# AIO.net
KiCad netlist of a schematic drawn in EAGLE
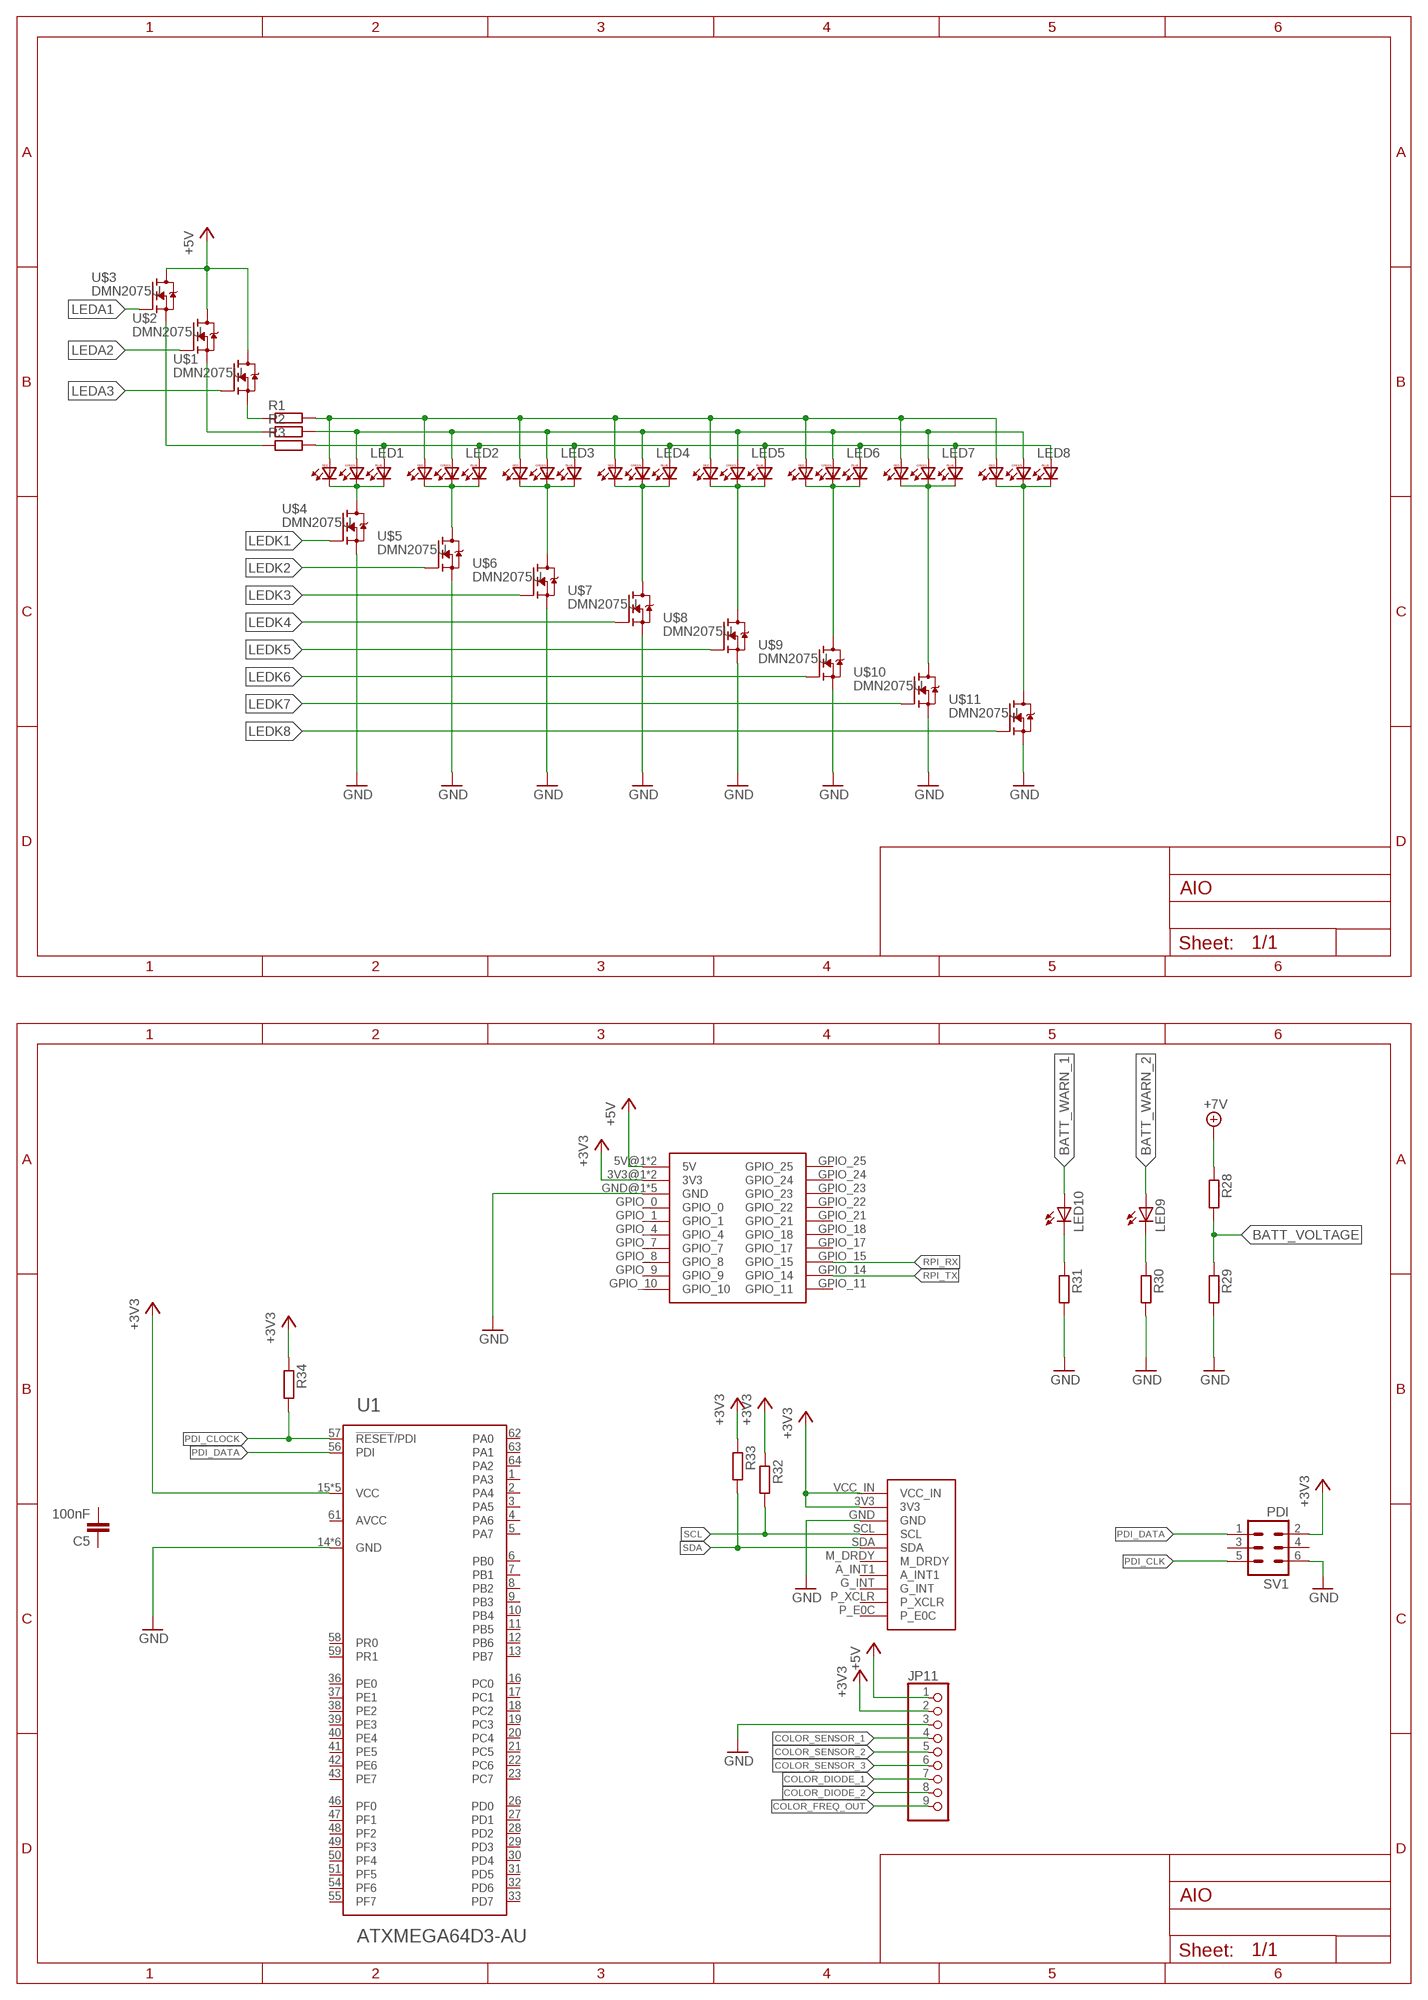
[diagram p0: schematic, sheet 1, part 1 of 2]
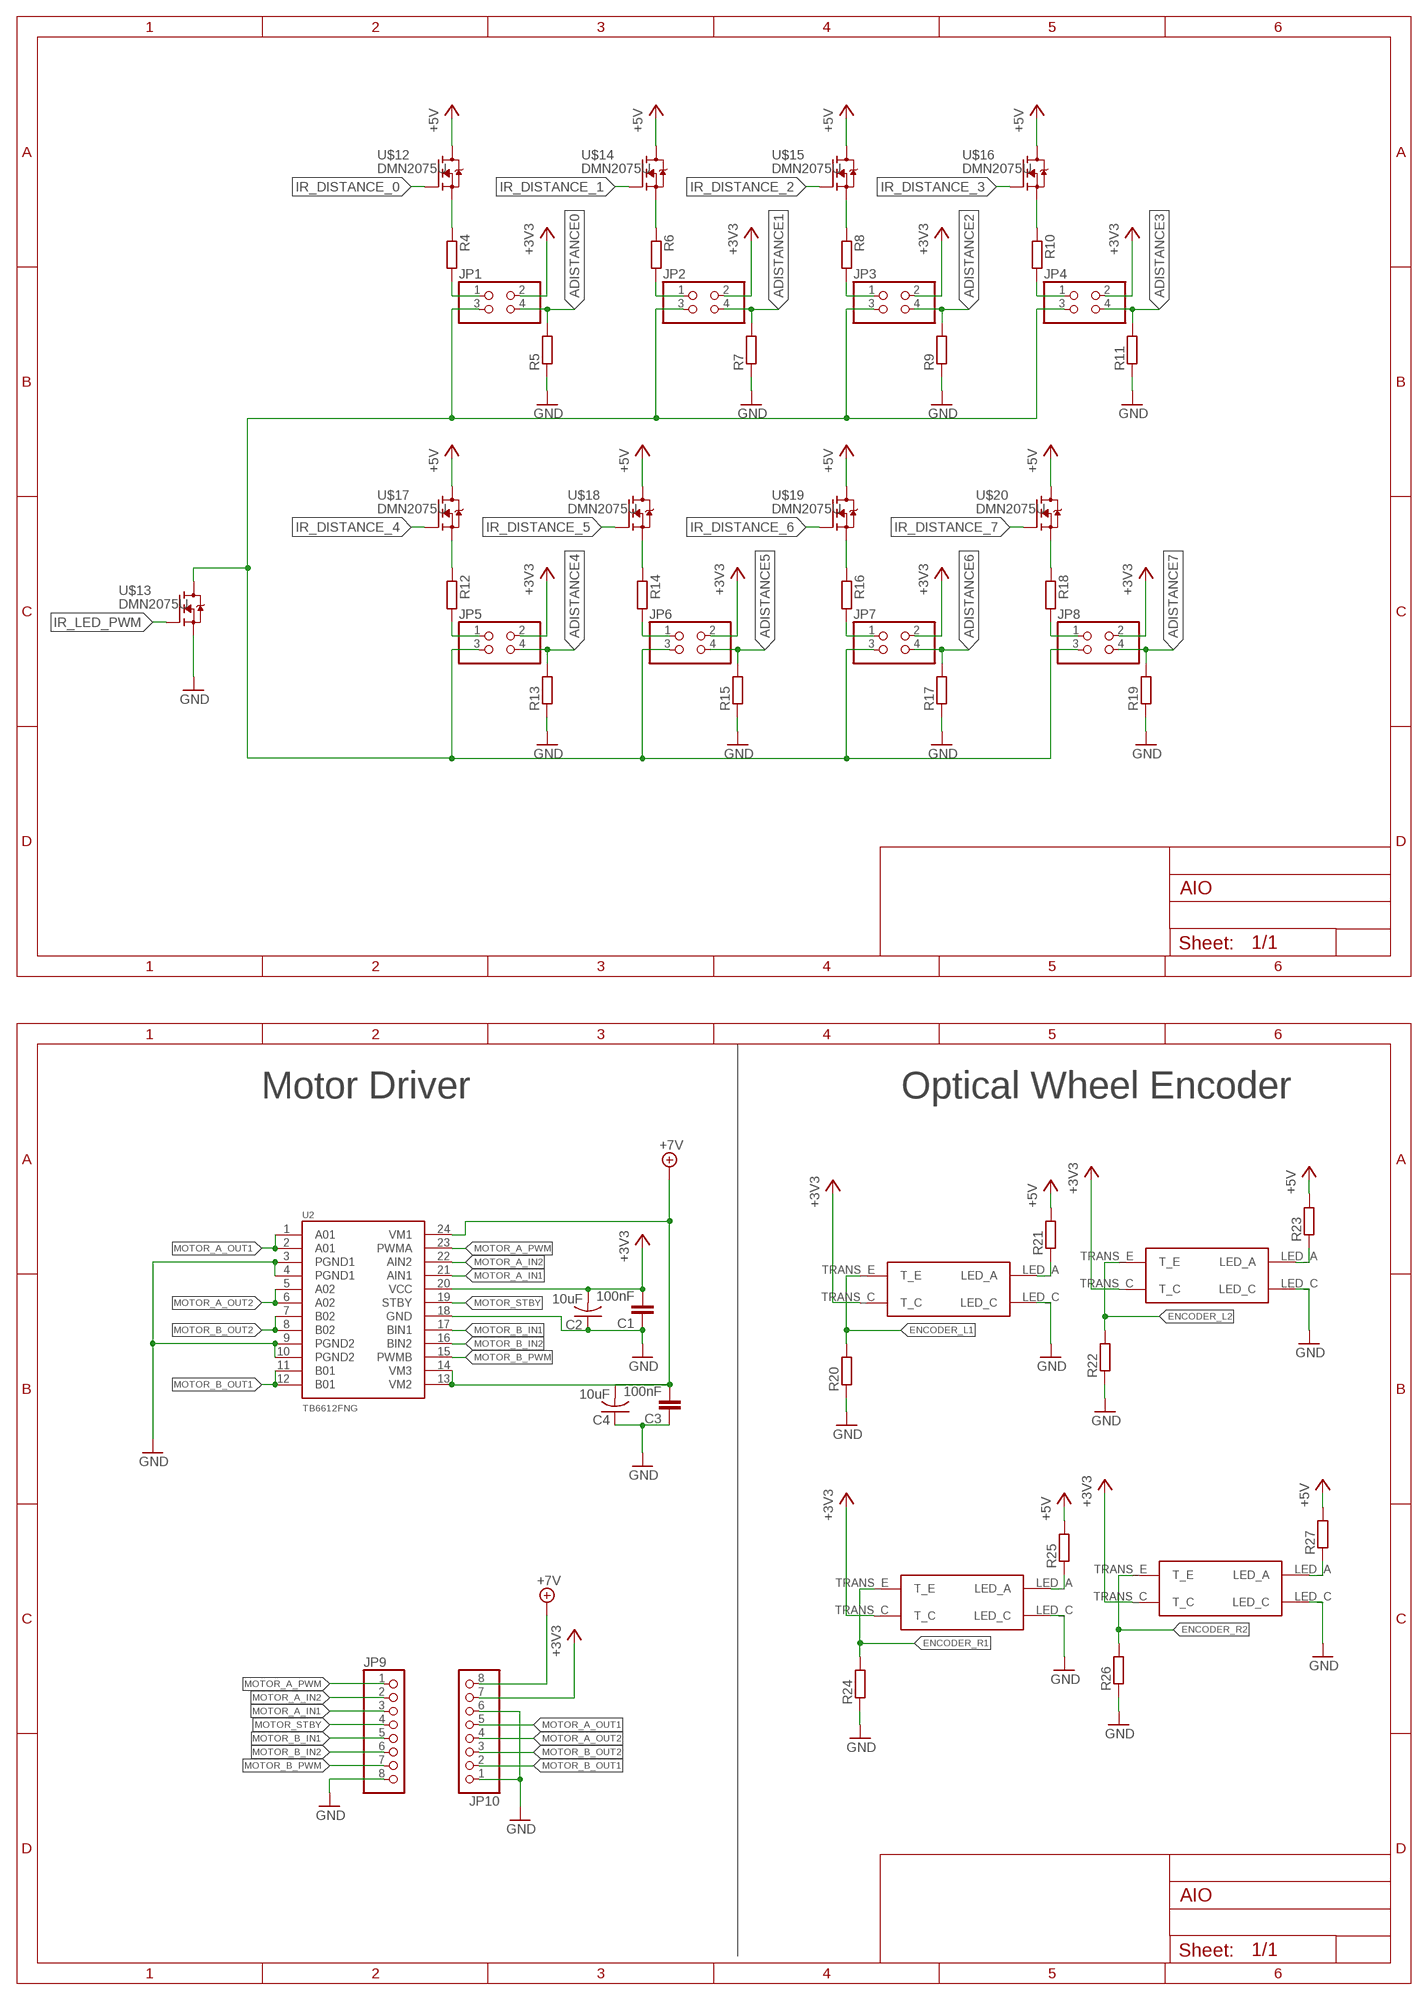
[diagram p1: schematic, sheet 1, part 2 of 2]

(export (version "E")
  (design (tool "Eeschema 10.0.6"))
  (components
    (comp (ref "C1")
      (value "100nF")
      (footprint "eagle-import:C0402")
      (libsource (lib "eagle-import") (part "C-EUC0402"))
    )
    (comp (ref "C2")
      (value "10uF")
      (footprint "eagle-import:C0402")
      (libsource (lib "eagle-import") (part "C-USC0402"))
    )
    (comp (ref "C3")
      (value "100nF")
      (footprint "eagle-import:C0402")
      (libsource (lib "eagle-import") (part "C-EUC0402"))
    )
    (comp (ref "C4")
      (value "10uF")
      (footprint "eagle-import:C0402")
      (libsource (lib "eagle-import") (part "C-USC0402"))
    )
    (comp (ref "C5")
      (value "100nF")
      (footprint "eagle-import:C0402")
      (libsource (lib "eagle-import") (part "C-EUC0402"))
    )
    (comp (ref "JP1")
      (value "PINHD-2X2/90")
      (footprint "eagle-import:2X02_90")
      (libsource (lib "eagle-import") (part "PINHD-2X2/90"))
    )
    (comp (ref "JP2")
      (value "PINHD-2X2/90")
      (footprint "eagle-import:2X02_90")
      (libsource (lib "eagle-import") (part "PINHD-2X2/90"))
    )
    (comp (ref "JP3")
      (value "PINHD-2X2/90")
      (footprint "eagle-import:2X02_90")
      (libsource (lib "eagle-import") (part "PINHD-2X2/90"))
    )
    (comp (ref "JP4")
      (value "PINHD-2X2/90")
      (footprint "eagle-import:2X02_90")
      (libsource (lib "eagle-import") (part "PINHD-2X2/90"))
    )
    (comp (ref "JP5")
      (value "PINHD-2X2/90")
      (footprint "eagle-import:2X02_90")
      (libsource (lib "eagle-import") (part "PINHD-2X2/90"))
    )
    (comp (ref "JP6")
      (value "PINHD-2X2/90")
      (footprint "eagle-import:2X02_90")
      (libsource (lib "eagle-import") (part "PINHD-2X2/90"))
    )
    (comp (ref "JP7")
      (value "PINHD-2X2/90")
      (footprint "eagle-import:2X02_90")
      (libsource (lib "eagle-import") (part "PINHD-2X2/90"))
    )
    (comp (ref "JP8")
      (value "PINHD-2X2/90")
      (footprint "eagle-import:2X02_90")
      (libsource (lib "eagle-import") (part "PINHD-2X2/90"))
    )
    (comp (ref "JP9")
      (value "PINHD-1X8")
      (footprint "eagle-import:1X08")
      (libsource (lib "eagle-import") (part "PINHD-1X8"))
    )
    (comp (ref "JP10")
      (value "PINHD-1X8")
      (footprint "eagle-import:1X08")
      (libsource (lib "eagle-import") (part "PINHD-1X8"))
    )
    (comp (ref "JP11")
      (value "PINHD-1X9")
      (footprint "eagle-import:1X09")
      (libsource (lib "eagle-import") (part "PINHD-1X9"))
    )
    (comp (ref "LED1")
      (value "F503605050")
      (footprint "eagle-import:5050LED")
      (libsource (lib "eagle-import") (part "F503605050"))
    )
    (comp (ref "LED2")
      (value "F503605050")
      (footprint "eagle-import:5050LED")
      (libsource (lib "eagle-import") (part "F503605050"))
    )
    (comp (ref "LED3")
      (value "F503605050")
      (footprint "eagle-import:5050LED")
      (libsource (lib "eagle-import") (part "F503605050"))
    )
    (comp (ref "LED4")
      (value "F503605050")
      (footprint "eagle-import:5050LED")
      (libsource (lib "eagle-import") (part "F503605050"))
    )
    (comp (ref "LED5")
      (value "F503605050")
      (footprint "eagle-import:5050LED")
      (libsource (lib "eagle-import") (part "F503605050"))
    )
    (comp (ref "LED6")
      (value "F503605050")
      (footprint "eagle-import:5050LED")
      (libsource (lib "eagle-import") (part "F503605050"))
    )
    (comp (ref "LED7")
      (value "F503605050")
      (footprint "eagle-import:5050LED")
      (libsource (lib "eagle-import") (part "F503605050"))
    )
    (comp (ref "LED8")
      (value "F503605050")
      (footprint "eagle-import:5050LED")
      (libsource (lib "eagle-import") (part "F503605050"))
    )
    (comp (ref "LED9")
      (value "LEDCHIPLED_0603")
      (footprint "eagle-import:CHIPLED_0603")
      (libsource (lib "eagle-import") (part "LEDCHIPLED_0603"))
    )
    (comp (ref "LED10")
      (value "LEDCHIPLED_0603")
      (footprint "eagle-import:CHIPLED_0603")
      (libsource (lib "eagle-import") (part "LEDCHIPLED_0603"))
    )
    (comp (ref "R1")
      (value "R-EU_R0402")
      (footprint "eagle-import:R0402")
      (libsource (lib "eagle-import") (part "R-EU_R0402"))
    )
    (comp (ref "R2")
      (value "R-EU_R0402")
      (footprint "eagle-import:R0402")
      (libsource (lib "eagle-import") (part "R-EU_R0402"))
    )
    (comp (ref "R3")
      (value "R-EU_R0402")
      (footprint "eagle-import:R0402")
      (libsource (lib "eagle-import") (part "R-EU_R0402"))
    )
    (comp (ref "R4")
      (value "R-EU_R0402")
      (footprint "eagle-import:R0402")
      (libsource (lib "eagle-import") (part "R-EU_R0402"))
    )
    (comp (ref "R5")
      (value "R-EU_R0402")
      (footprint "eagle-import:R0402")
      (libsource (lib "eagle-import") (part "R-EU_R0402"))
    )
    (comp (ref "R6")
      (value "R-EU_R0402")
      (footprint "eagle-import:R0402")
      (libsource (lib "eagle-import") (part "R-EU_R0402"))
    )
    (comp (ref "R7")
      (value "R-EU_R0402")
      (footprint "eagle-import:R0402")
      (libsource (lib "eagle-import") (part "R-EU_R0402"))
    )
    (comp (ref "R8")
      (value "R-EU_R0402")
      (footprint "eagle-import:R0402")
      (libsource (lib "eagle-import") (part "R-EU_R0402"))
    )
    (comp (ref "R9")
      (value "R-EU_R0402")
      (footprint "eagle-import:R0402")
      (libsource (lib "eagle-import") (part "R-EU_R0402"))
    )
    (comp (ref "R10")
      (value "R-EU_R0402")
      (footprint "eagle-import:R0402")
      (libsource (lib "eagle-import") (part "R-EU_R0402"))
    )
    (comp (ref "R11")
      (value "R-EU_R0402")
      (footprint "eagle-import:R0402")
      (libsource (lib "eagle-import") (part "R-EU_R0402"))
    )
    (comp (ref "R12")
      (value "R-EU_R0402")
      (footprint "eagle-import:R0402")
      (libsource (lib "eagle-import") (part "R-EU_R0402"))
    )
    (comp (ref "R13")
      (value "R-EU_R0402")
      (footprint "eagle-import:R0402")
      (libsource (lib "eagle-import") (part "R-EU_R0402"))
    )
    (comp (ref "R14")
      (value "R-EU_R0402")
      (footprint "eagle-import:R0402")
      (libsource (lib "eagle-import") (part "R-EU_R0402"))
    )
    (comp (ref "R15")
      (value "R-EU_R0402")
      (footprint "eagle-import:R0402")
      (libsource (lib "eagle-import") (part "R-EU_R0402"))
    )
    (comp (ref "R16")
      (value "R-EU_R0402")
      (footprint "eagle-import:R0402")
      (libsource (lib "eagle-import") (part "R-EU_R0402"))
    )
    (comp (ref "R17")
      (value "R-EU_R0402")
      (footprint "eagle-import:R0402")
      (libsource (lib "eagle-import") (part "R-EU_R0402"))
    )
    (comp (ref "R18")
      (value "R-EU_R0402")
      (footprint "eagle-import:R0402")
      (libsource (lib "eagle-import") (part "R-EU_R0402"))
    )
    (comp (ref "R19")
      (value "R-EU_R0402")
      (footprint "eagle-import:R0402")
      (libsource (lib "eagle-import") (part "R-EU_R0402"))
    )
    (comp (ref "R20")
      (value "R-EU_R0402")
      (footprint "eagle-import:R0402")
      (libsource (lib "eagle-import") (part "R-EU_R0402"))
    )
    (comp (ref "R21")
      (value "R-EU_R0402")
      (footprint "eagle-import:R0402")
      (libsource (lib "eagle-import") (part "R-EU_R0402"))
    )
    (comp (ref "R22")
      (value "R-EU_R0402")
      (footprint "eagle-import:R0402")
      (libsource (lib "eagle-import") (part "R-EU_R0402"))
    )
    (comp (ref "R23")
      (value "R-EU_R0402")
      (footprint "eagle-import:R0402")
      (libsource (lib "eagle-import") (part "R-EU_R0402"))
    )
    (comp (ref "R24")
      (value "R-EU_R0402")
      (footprint "eagle-import:R0402")
      (libsource (lib "eagle-import") (part "R-EU_R0402"))
    )
    (comp (ref "R25")
      (value "R-EU_R0402")
      (footprint "eagle-import:R0402")
      (libsource (lib "eagle-import") (part "R-EU_R0402"))
    )
    (comp (ref "R26")
      (value "R-EU_R0402")
      (footprint "eagle-import:R0402")
      (libsource (lib "eagle-import") (part "R-EU_R0402"))
    )
    (comp (ref "R27")
      (value "R-EU_R0402")
      (footprint "eagle-import:R0402")
      (libsource (lib "eagle-import") (part "R-EU_R0402"))
    )
    (comp (ref "R28")
      (value "R-EU_R0402")
      (footprint "eagle-import:R0402")
      (libsource (lib "eagle-import") (part "R-EU_R0402"))
    )
    (comp (ref "R29")
      (value "R-EU_R0402")
      (footprint "eagle-import:R0402")
      (libsource (lib "eagle-import") (part "R-EU_R0402"))
    )
    (comp (ref "R30")
      (value "R-EU_R0402")
      (footprint "eagle-import:R0402")
      (libsource (lib "eagle-import") (part "R-EU_R0402"))
    )
    (comp (ref "R31")
      (value "R-EU_R0402")
      (footprint "eagle-import:R0402")
      (libsource (lib "eagle-import") (part "R-EU_R0402"))
    )
    (comp (ref "R32")
      (value "R-EU_R0402")
      (footprint "eagle-import:R0402")
      (libsource (lib "eagle-import") (part "R-EU_R0402"))
    )
    (comp (ref "R33")
      (value "R-EU_R0402")
      (footprint "eagle-import:R0402")
      (libsource (lib "eagle-import") (part "R-EU_R0402"))
    )
    (comp (ref "R34")
      (value "R-EU_R0402")
      (footprint "eagle-import:R0402")
      (libsource (lib "eagle-import") (part "R-EU_R0402"))
    )
    (comp (ref "SV1")
      (value "PDI")
      (footprint "eagle-import:ML6")
      (libsource (lib "eagle-import") (part "ML6"))
    )
    (comp (ref "U$1")
      (value "DMN2075U")
      (footprint "eagle-import:SOT95P240X112-3N")
      (libsource (lib "eagle-import") (part "DMN2075U"))
    )
    (comp (ref "U$2")
      (value "DMN2075U")
      (footprint "eagle-import:SOT95P240X112-3N")
      (libsource (lib "eagle-import") (part "DMN2075U"))
    )
    (comp (ref "U$3")
      (value "DMN2075U")
      (footprint "eagle-import:SOT95P240X112-3N")
      (libsource (lib "eagle-import") (part "DMN2075U"))
    )
    (comp (ref "U$4")
      (value "DMN2075U")
      (footprint "eagle-import:SOT95P240X112-3N")
      (libsource (lib "eagle-import") (part "DMN2075U"))
    )
    (comp (ref "U$5")
      (value "DMN2075U")
      (footprint "eagle-import:SOT95P240X112-3N")
      (libsource (lib "eagle-import") (part "DMN2075U"))
    )
    (comp (ref "U$6")
      (value "DMN2075U")
      (footprint "eagle-import:SOT95P240X112-3N")
      (libsource (lib "eagle-import") (part "DMN2075U"))
    )
    (comp (ref "U$7")
      (value "DMN2075U")
      (footprint "eagle-import:SOT95P240X112-3N")
      (libsource (lib "eagle-import") (part "DMN2075U"))
    )
    (comp (ref "U$8")
      (value "DMN2075U")
      (footprint "eagle-import:SOT95P240X112-3N")
      (libsource (lib "eagle-import") (part "DMN2075U"))
    )
    (comp (ref "U$9")
      (value "DMN2075U")
      (footprint "eagle-import:SOT95P240X112-3N")
      (libsource (lib "eagle-import") (part "DMN2075U"))
    )
    (comp (ref "U$10")
      (value "DMN2075U")
      (footprint "eagle-import:SOT95P240X112-3N")
      (libsource (lib "eagle-import") (part "DMN2075U"))
    )
    (comp (ref "U$11")
      (value "DMN2075U")
      (footprint "eagle-import:SOT95P240X112-3N")
      (libsource (lib "eagle-import") (part "DMN2075U"))
    )
    (comp (ref "U$12")
      (value "DMN2075U")
      (footprint "eagle-import:SOT95P240X112-3N")
      (libsource (lib "eagle-import") (part "DMN2075U"))
    )
    (comp (ref "U$13")
      (value "DMN2075U")
      (footprint "eagle-import:SOT95P240X112-3N")
      (libsource (lib "eagle-import") (part "DMN2075U"))
    )
    (comp (ref "U$14")
      (value "DMN2075U")
      (footprint "eagle-import:SOT95P240X112-3N")
      (libsource (lib "eagle-import") (part "DMN2075U"))
    )
    (comp (ref "U$15")
      (value "DMN2075U")
      (footprint "eagle-import:SOT95P240X112-3N")
      (libsource (lib "eagle-import") (part "DMN2075U"))
    )
    (comp (ref "U$16")
      (value "DMN2075U")
      (footprint "eagle-import:SOT95P240X112-3N")
      (libsource (lib "eagle-import") (part "DMN2075U"))
    )
    (comp (ref "U$17")
      (value "DMN2075U")
      (footprint "eagle-import:SOT95P240X112-3N")
      (libsource (lib "eagle-import") (part "DMN2075U"))
    )
    (comp (ref "U$18")
      (value "DMN2075U")
      (footprint "eagle-import:SOT95P240X112-3N")
      (libsource (lib "eagle-import") (part "DMN2075U"))
    )
    (comp (ref "U$19")
      (value "DMN2075U")
      (footprint "eagle-import:SOT95P240X112-3N")
      (libsource (lib "eagle-import") (part "DMN2075U"))
    )
    (comp (ref "U$20")
      (value "DMN2075U")
      (footprint "eagle-import:SOT95P240X112-3N")
      (libsource (lib "eagle-import") (part "DMN2075U"))
    )
    (comp (ref "U$21")
      (value "CNY70")
      (footprint "eagle-import:CNY70")
      (libsource (lib "eagle-import") (part "CNY70"))
    )
    (comp (ref "U$22")
      (value "CNY70")
      (footprint "eagle-import:CNY70")
      (libsource (lib "eagle-import") (part "CNY70"))
    )
    (comp (ref "U$23")
      (value "CNY70")
      (footprint "eagle-import:CNY70")
      (libsource (lib "eagle-import") (part "CNY70"))
    )
    (comp (ref "U$24")
      (value "CNY70")
      (footprint "eagle-import:CNY70")
      (libsource (lib "eagle-import") (part "CNY70"))
    )
    (comp (ref "U$25")
      (value "GY-81")
      (footprint "eagle-import:GY-81")
      (libsource (lib "eagle-import") (part "GY-81"))
    )
    (comp (ref "U$26")
      (value "RASPBERRY-PI")
      (footprint "eagle-import:RASPERRRY-PI")
      (libsource (lib "eagle-import") (part "RASPBERRY-PI"))
    )
    (comp (ref "U1")
      (value "ATXMEGA64D3-AU")
      (footprint "eagle-import:TQFP-64A-64")
      (libsource (lib "eagle-import") (part "ATXMEGA64D3-AU"))
    )
    (comp (ref "U2")
      (value "TB6612FNG")
      (footprint "eagle-import:SSOP24")
      (libsource (lib "eagle-import") (part "TB6621FNG"))
    )
  )
  (nets
    (net (code "1") (name "+3V3") (class "Default")
      (node (ref "C1") (pin "2") (pinfunction "2_2") (pintype "passive"))
      (node (ref "C2") (pin "2") (pinfunction "2_2") (pintype "passive"))
      (node (ref "JP1") (pin "2") (pinfunction "2_2") (pintype "passive"))
      (node (ref "JP10") (pin "7") (pinfunction "7_7") (pintype "passive"))
      (node (ref "JP11") (pin "2") (pinfunction "2_2") (pintype "passive"))
      (node (ref "JP2") (pin "2") (pinfunction "2_2") (pintype "passive"))
      (node (ref "JP3") (pin "2") (pinfunction "2_2") (pintype "passive"))
      (node (ref "JP4") (pin "2") (pinfunction "2_2") (pintype "passive"))
      (node (ref "JP5") (pin "2") (pinfunction "2_2") (pintype "passive"))
      (node (ref "JP6") (pin "2") (pinfunction "2_2") (pintype "passive"))
      (node (ref "JP7") (pin "2") (pinfunction "2_2") (pintype "passive"))
      (node (ref "JP8") (pin "2") (pinfunction "2_2") (pintype "passive"))
      (node (ref "R32") (pin "1") (pinfunction "1_1") (pintype "passive"))
      (node (ref "R33") (pin "1") (pinfunction "1_1") (pintype "passive"))
      (node (ref "R34") (pin "1") (pinfunction "1_1") (pintype "passive"))
      (node (ref "SV1") (pin "2") (pinfunction "2_2") (pintype "passive"))
      (node (ref "U$21") (pin "TRANS_C") (pinfunction "T_C_TRANS_C") (pintype "bidirectional"))
      (node (ref "U$22") (pin "TRANS_C") (pinfunction "T_C_TRANS_C") (pintype "bidirectional"))
      (node (ref "U$23") (pin "TRANS_C") (pinfunction "T_C_TRANS_C") (pintype "bidirectional"))
      (node (ref "U$24") (pin "TRANS_C") (pinfunction "T_C_TRANS_C") (pintype "bidirectional"))
      (node (ref "U$25") (pin "3V3") (pinfunction "3V3_3V3") (pintype "bidirectional"))
      (node (ref "U$25") (pin "VCC_IN") (pinfunction "VCC_IN_VCC_IN") (pintype "bidirectional"))
      (node (ref "U$26") (pin "3V3@1") (pinfunction "3V3_3V3@1") (pintype "power_in"))
      (node (ref "U$26") (pin "3V3@2") (pinfunction "3V3_3V3@2") (pintype "power_in"))
      (node (ref "U1") (pin "15") (pinfunction "VCC_15") (pintype "power_in"))
      (node (ref "U1") (pin "25") (pinfunction "VCC_25") (pintype "power_in"))
      (node (ref "U1") (pin "35") (pinfunction "VCC_35") (pintype "power_in"))
      (node (ref "U1") (pin "45") (pinfunction "VCC_45") (pintype "power_in"))
      (node (ref "U1") (pin "53") (pinfunction "VCC_53") (pintype "power_in"))
      (node (ref "U2") (pin "20") (pinfunction "VCC_20") (pintype "bidirectional"))
    )
    (net (code "2") (name "+5V") (class "Default")
      (node (ref "JP11") (pin "1") (pinfunction "1_1") (pintype "passive"))
      (node (ref "R21") (pin "2") (pinfunction "2_2") (pintype "passive"))
      (node (ref "R23") (pin "2") (pinfunction "2_2") (pintype "passive"))
      (node (ref "R25") (pin "2") (pinfunction "2_2") (pintype "passive"))
      (node (ref "R27") (pin "2") (pinfunction "2_2") (pintype "passive"))
      (node (ref "U$1") (pin "D") (pinfunction "D_D") (pintype "passive"))
      (node (ref "U$12") (pin "D") (pinfunction "D_D") (pintype "passive"))
      (node (ref "U$14") (pin "D") (pinfunction "D_D") (pintype "passive"))
      (node (ref "U$15") (pin "D") (pinfunction "D_D") (pintype "passive"))
      (node (ref "U$16") (pin "D") (pinfunction "D_D") (pintype "passive"))
      (node (ref "U$17") (pin "D") (pinfunction "D_D") (pintype "passive"))
      (node (ref "U$18") (pin "D") (pinfunction "D_D") (pintype "passive"))
      (node (ref "U$19") (pin "D") (pinfunction "D_D") (pintype "passive"))
      (node (ref "U$2") (pin "D") (pinfunction "D_D") (pintype "passive"))
      (node (ref "U$20") (pin "D") (pinfunction "D_D") (pintype "passive"))
      (node (ref "U$26") (pin "5V@1") (pinfunction "5V_5V@1") (pintype "power_in"))
      (node (ref "U$26") (pin "5V@2") (pinfunction "5V_5V@2") (pintype "power_in"))
      (node (ref "U$3") (pin "D") (pinfunction "D_D") (pintype "passive"))
    )
    (net (code "3") (name "+7V") (class "Default")
      (node (ref "C3") (pin "2") (pinfunction "2_2") (pintype "passive"))
      (node (ref "C4") (pin "2") (pinfunction "2_2") (pintype "passive"))
      (node (ref "JP10") (pin "8") (pinfunction "8_8") (pintype "passive"))
      (node (ref "R28") (pin "1") (pinfunction "1_1") (pintype "passive"))
      (node (ref "U2") (pin "13") (pinfunction "VM2_13") (pintype "bidirectional"))
      (node (ref "U2") (pin "14") (pinfunction "VM3_14") (pintype "bidirectional"))
      (node (ref "U2") (pin "24") (pinfunction "VM1_24") (pintype "bidirectional"))
    )
    (net (code "4") (name "/AVCC") (class "Default")
      (node (ref "U1") (pin "61") (pinfunction "AVCC_61") (pintype "power_in"))
    )
    (net (code "5") (name "ADISTANCE0") (class "Default")
      (node (ref "JP1") (pin "4") (pinfunction "4_4") (pintype "passive"))
      (node (ref "R5") (pin "2") (pinfunction "2_2") (pintype "passive"))
    )
    (net (code "6") (name "ADISTANCE1") (class "Default")
      (node (ref "JP2") (pin "4") (pinfunction "4_4") (pintype "passive"))
      (node (ref "R7") (pin "2") (pinfunction "2_2") (pintype "passive"))
    )
    (net (code "7") (name "ADISTANCE2") (class "Default")
      (node (ref "JP3") (pin "4") (pinfunction "4_4") (pintype "passive"))
      (node (ref "R9") (pin "2") (pinfunction "2_2") (pintype "passive"))
    )
    (net (code "8") (name "ADISTANCE3") (class "Default")
      (node (ref "JP4") (pin "4") (pinfunction "4_4") (pintype "passive"))
      (node (ref "R11") (pin "2") (pinfunction "2_2") (pintype "passive"))
    )
    (net (code "9") (name "ADISTANCE4") (class "Default")
      (node (ref "JP5") (pin "4") (pinfunction "4_4") (pintype "passive"))
      (node (ref "R13") (pin "2") (pinfunction "2_2") (pintype "passive"))
    )
    (net (code "10") (name "ADISTANCE5") (class "Default")
      (node (ref "JP6") (pin "4") (pinfunction "4_4") (pintype "passive"))
      (node (ref "R15") (pin "2") (pinfunction "2_2") (pintype "passive"))
    )
    (net (code "11") (name "ADISTANCE6") (class "Default")
      (node (ref "JP7") (pin "4") (pinfunction "4_4") (pintype "passive"))
      (node (ref "R17") (pin "2") (pinfunction "2_2") (pintype "passive"))
    )
    (net (code "12") (name "ADISTANCE7") (class "Default")
      (node (ref "JP8") (pin "4") (pinfunction "4_4") (pintype "passive"))
      (node (ref "R19") (pin "2") (pinfunction "2_2") (pintype "passive"))
    )
    (net (code "13") (name "BATT_VOLTAGE") (class "Default")
      (node (ref "R28") (pin "2") (pinfunction "2_2") (pintype "passive"))
      (node (ref "R29") (pin "1") (pinfunction "1_1") (pintype "passive"))
    )
    (net (code "14") (name "BATT_WARN_1") (class "Default")
      (node (ref "LED10") (pin "A") (pinfunction "A_A") (pintype "passive"))
    )
    (net (code "15") (name "BATT_WARN_2") (class "Default")
      (node (ref "LED9") (pin "A") (pinfunction "A_A") (pintype "passive"))
    )
    (net (code "16") (name "COLOR_DIODE_1") (class "Default")
      (node (ref "JP11") (pin "7") (pinfunction "7_7") (pintype "passive"))
    )
    (net (code "17") (name "COLOR_DIODE_2") (class "Default")
      (node (ref "JP11") (pin "8") (pinfunction "8_8") (pintype "passive"))
    )
    (net (code "18") (name "COLOR_FREQ_OUT") (class "Default")
      (node (ref "JP11") (pin "9") (pinfunction "9_9") (pintype "passive"))
    )
    (net (code "19") (name "COLOR_SENSOR_1") (class "Default")
      (node (ref "JP11") (pin "4") (pinfunction "4_4") (pintype "passive"))
    )
    (net (code "20") (name "COLOR_SENSOR_2") (class "Default")
      (node (ref "JP11") (pin "5") (pinfunction "5_5") (pintype "passive"))
    )
    (net (code "21") (name "COLOR_SENSOR_3") (class "Default")
      (node (ref "JP11") (pin "6") (pinfunction "6_6") (pintype "passive"))
    )
    (net (code "22") (name "ENCODER_L1") (class "Default")
      (node (ref "R20") (pin "2") (pinfunction "2_2") (pintype "passive"))
      (node (ref "U$21") (pin "TRANS_E") (pinfunction "T_E_TRANS_E") (pintype "bidirectional"))
    )
    (net (code "23") (name "ENCODER_L2") (class "Default")
      (node (ref "R22") (pin "2") (pinfunction "2_2") (pintype "passive"))
      (node (ref "U$22") (pin "TRANS_E") (pinfunction "T_E_TRANS_E") (pintype "bidirectional"))
    )
    (net (code "24") (name "ENCODER_R1") (class "Default")
      (node (ref "R24") (pin "2") (pinfunction "2_2") (pintype "passive"))
      (node (ref "U$23") (pin "TRANS_E") (pinfunction "T_E_TRANS_E") (pintype "bidirectional"))
    )
    (net (code "25") (name "ENCODER_R2") (class "Default")
      (node (ref "R26") (pin "2") (pinfunction "2_2") (pintype "passive"))
      (node (ref "U$24") (pin "TRANS_E") (pinfunction "T_E_TRANS_E") (pintype "bidirectional"))
    )
    (net (code "26") (name "GND") (class "Default")
      (node (ref "C1") (pin "1") (pinfunction "1_1") (pintype "passive"))
      (node (ref "C2") (pin "1") (pinfunction "1_1") (pintype "passive"))
      (node (ref "C3") (pin "1") (pinfunction "1_1") (pintype "passive"))
      (node (ref "C4") (pin "1") (pinfunction "1_1") (pintype "passive"))
      (node (ref "JP10") (pin "1") (pinfunction "1_1") (pintype "passive"))
      (node (ref "JP10") (pin "6") (pinfunction "6_6") (pintype "passive"))
      (node (ref "JP11") (pin "3") (pinfunction "3_3") (pintype "passive"))
      (node (ref "JP9") (pin "8") (pinfunction "8_8") (pintype "passive"))
      (node (ref "R11") (pin "1") (pinfunction "1_1") (pintype "passive"))
      (node (ref "R13") (pin "1") (pinfunction "1_1") (pintype "passive"))
      (node (ref "R15") (pin "1") (pinfunction "1_1") (pintype "passive"))
      (node (ref "R17") (pin "1") (pinfunction "1_1") (pintype "passive"))
      (node (ref "R19") (pin "1") (pinfunction "1_1") (pintype "passive"))
      (node (ref "R20") (pin "1") (pinfunction "1_1") (pintype "passive"))
      (node (ref "R22") (pin "1") (pinfunction "1_1") (pintype "passive"))
      (node (ref "R24") (pin "1") (pinfunction "1_1") (pintype "passive"))
      (node (ref "R26") (pin "1") (pinfunction "1_1") (pintype "passive"))
      (node (ref "R29") (pin "2") (pinfunction "2_2") (pintype "passive"))
      (node (ref "R30") (pin "2") (pinfunction "2_2") (pintype "passive"))
      (node (ref "R31") (pin "2") (pinfunction "2_2") (pintype "passive"))
      (node (ref "R5") (pin "1") (pinfunction "1_1") (pintype "passive"))
      (node (ref "R7") (pin "1") (pinfunction "1_1") (pintype "passive"))
      (node (ref "R9") (pin "1") (pinfunction "1_1") (pintype "passive"))
      (node (ref "SV1") (pin "6") (pinfunction "6_6") (pintype "passive"))
      (node (ref "U$10") (pin "S") (pinfunction "S_S") (pintype "passive"))
      (node (ref "U$11") (pin "S") (pinfunction "S_S") (pintype "passive"))
      (node (ref "U$13") (pin "S") (pinfunction "S_S") (pintype "passive"))
      (node (ref "U$21") (pin "LED_C") (pinfunction "LED_C_LED_C") (pintype "bidirectional"))
      (node (ref "U$22") (pin "LED_C") (pinfunction "LED_C_LED_C") (pintype "bidirectional"))
      (node (ref "U$23") (pin "LED_C") (pinfunction "LED_C_LED_C") (pintype "bidirectional"))
      (node (ref "U$24") (pin "LED_C") (pinfunction "LED_C_LED_C") (pintype "bidirectional"))
      (node (ref "U$25") (pin "GND") (pinfunction "GND_GND") (pintype "bidirectional"))
      (node (ref "U$26") (pin "GND@1") (pinfunction "GND_GND@1") (pintype "power_in"))
      (node (ref "U$26") (pin "GND@2") (pinfunction "GND_GND@2") (pintype "power_in"))
      (node (ref "U$26") (pin "GND@3") (pinfunction "GND_GND@3") (pintype "power_in"))
      (node (ref "U$26") (pin "GND@4") (pinfunction "GND_GND@4") (pintype "power_in"))
      (node (ref "U$26") (pin "GND@5") (pinfunction "GND_GND@5") (pintype "power_in"))
      (node (ref "U$4") (pin "S") (pinfunction "S_S") (pintype "passive"))
      (node (ref "U$5") (pin "S") (pinfunction "S_S") (pintype "passive"))
      (node (ref "U$6") (pin "S") (pinfunction "S_S") (pintype "passive"))
      (node (ref "U$7") (pin "S") (pinfunction "S_S") (pintype "passive"))
      (node (ref "U$8") (pin "S") (pinfunction "S_S") (pintype "passive"))
      (node (ref "U$9") (pin "S") (pinfunction "S_S") (pintype "passive"))
      (node (ref "U1") (pin "14") (pinfunction "GND_14") (pintype "power_in"))
      (node (ref "U1") (pin "24") (pinfunction "GND_24") (pintype "power_in"))
      (node (ref "U1") (pin "34") (pinfunction "GND_34") (pintype "power_in"))
      (node (ref "U1") (pin "44") (pinfunction "GND_44") (pintype "power_in"))
      (node (ref "U1") (pin "52") (pinfunction "GND_52") (pintype "power_in"))
      (node (ref "U1") (pin "60") (pinfunction "GND_60") (pintype "power_in"))
      (node (ref "U2") (pin "10") (pinfunction "PGND2_10") (pintype "bidirectional"))
      (node (ref "U2") (pin "18") (pinfunction "GND_18") (pintype "bidirectional"))
      (node (ref "U2") (pin "3") (pinfunction "PGND1_3") (pintype "bidirectional"))
      (node (ref "U2") (pin "4") (pinfunction "PGND1_4") (pintype "bidirectional"))
      (node (ref "U2") (pin "9") (pinfunction "PGND2_9") (pintype "bidirectional"))
    )
    (net (code "27") (name "IR_DISTANCE_0") (class "Default")
      (node (ref "U$12") (pin "G") (pinfunction "G_G") (pintype "passive"))
    )
    (net (code "28") (name "IR_DISTANCE_1") (class "Default")
      (node (ref "U$14") (pin "G") (pinfunction "G_G") (pintype "passive"))
    )
    (net (code "29") (name "IR_DISTANCE_2") (class "Default")
      (node (ref "U$15") (pin "G") (pinfunction "G_G") (pintype "passive"))
    )
    (net (code "30") (name "IR_DISTANCE_3") (class "Default")
      (node (ref "U$16") (pin "G") (pinfunction "G_G") (pintype "passive"))
    )
    (net (code "31") (name "IR_DISTANCE_4") (class "Default")
      (node (ref "U$17") (pin "G") (pinfunction "G_G") (pintype "passive"))
    )
    (net (code "32") (name "IR_DISTANCE_5") (class "Default")
      (node (ref "U$18") (pin "G") (pinfunction "G_G") (pintype "passive"))
    )
    (net (code "33") (name "IR_DISTANCE_6") (class "Default")
      (node (ref "U$19") (pin "G") (pinfunction "G_G") (pintype "passive"))
    )
    (net (code "34") (name "IR_DISTANCE_7") (class "Default")
      (node (ref "U$20") (pin "G") (pinfunction "G_G") (pintype "passive"))
    )
    (net (code "35") (name "IR_LED_PWM") (class "Default")
      (node (ref "U$13") (pin "G") (pinfunction "G_G") (pintype "passive"))
    )
    (net (code "36") (name "LEDA1") (class "Default")
      (node (ref "U$3") (pin "G") (pinfunction "G_G") (pintype "passive"))
    )
    (net (code "37") (name "LEDA2") (class "Default")
      (node (ref "U$2") (pin "G") (pinfunction "G_G") (pintype "passive"))
    )
    (net (code "38") (name "LEDA3") (class "Default")
      (node (ref "U$1") (pin "G") (pinfunction "G_G") (pintype "passive"))
    )
    (net (code "39") (name "LEDK1") (class "Default")
      (node (ref "U$4") (pin "G") (pinfunction "G_G") (pintype "passive"))
    )
    (net (code "40") (name "LEDK2") (class "Default")
      (node (ref "U$5") (pin "G") (pinfunction "G_G") (pintype "passive"))
    )
    (net (code "41") (name "LEDK3") (class "Default")
      (node (ref "U$6") (pin "G") (pinfunction "G_G") (pintype "passive"))
    )
    (net (code "42") (name "LEDK4") (class "Default")
      (node (ref "U$7") (pin "G") (pinfunction "G_G") (pintype "passive"))
    )
    (net (code "43") (name "LEDK5") (class "Default")
      (node (ref "U$8") (pin "G") (pinfunction "G_G") (pintype "passive"))
    )
    (net (code "44") (name "LEDK6") (class "Default")
      (node (ref "U$9") (pin "G") (pinfunction "G_G") (pintype "passive"))
    )
    (net (code "45") (name "LEDK7") (class "Default")
      (node (ref "U$10") (pin "G") (pinfunction "G_G") (pintype "passive"))
    )
    (net (code "46") (name "LEDK8") (class "Default")
      (node (ref "U$11") (pin "G") (pinfunction "G_G") (pintype "passive"))
    )
    (net (code "47") (name "MOTOR_A_IN1") (class "Default")
      (node (ref "JP9") (pin "3") (pinfunction "3_3") (pintype "passive"))
      (node (ref "U2") (pin "21") (pinfunction "AIN1_21") (pintype "bidirectional"))
    )
    (net (code "48") (name "MOTOR_A_IN2") (class "Default")
      (node (ref "JP9") (pin "2") (pinfunction "2_2") (pintype "passive"))
      (node (ref "U2") (pin "22") (pinfunction "AIN2_22") (pintype "bidirectional"))
    )
    (net (code "49") (name "MOTOR_A_OUT1") (class "Default")
      (node (ref "JP10") (pin "5") (pinfunction "5_5") (pintype "passive"))
      (node (ref "U2") (pin "1") (pinfunction "A01_1") (pintype "bidirectional"))
      (node (ref "U2") (pin "2") (pinfunction "A01_2") (pintype "bidirectional"))
    )
    (net (code "50") (name "MOTOR_A_OUT2") (class "Default")
      (node (ref "JP10") (pin "4") (pinfunction "4_4") (pintype "passive"))
      (node (ref "U2") (pin "5") (pinfunction "A02_5") (pintype "bidirectional"))
      (node (ref "U2") (pin "6") (pinfunction "A02_6") (pintype "bidirectional"))
    )
    (net (code "51") (name "MOTOR_A_PWM") (class "Default")
      (node (ref "JP9") (pin "1") (pinfunction "1_1") (pintype "passive"))
      (node (ref "U2") (pin "23") (pinfunction "PWMA_23") (pintype "bidirectional"))
    )
    (net (code "52") (name "MOTOR_B_IN1") (class "Default")
      (node (ref "JP9") (pin "5") (pinfunction "5_5") (pintype "passive"))
      (node (ref "U2") (pin "17") (pinfunction "BIN1_17") (pintype "bidirectional"))
    )
    (net (code "53") (name "MOTOR_B_IN2") (class "Default")
      (node (ref "JP9") (pin "6") (pinfunction "6_6") (pintype "passive"))
      (node (ref "U2") (pin "16") (pinfunction "BIN2_16") (pintype "bidirectional"))
    )
    (net (code "54") (name "MOTOR_B_OUT1") (class "Default")
      (node (ref "JP10") (pin "2") (pinfunction "2_2") (pintype "passive"))
      (node (ref "U2") (pin "11") (pinfunction "B01_11") (pintype "bidirectional"))
      (node (ref "U2") (pin "12") (pinfunction "B01_12") (pintype "bidirectional"))
    )
    (net (code "55") (name "MOTOR_B_OUT2") (class "Default")
      (node (ref "JP10") (pin "3") (pinfunction "3_3") (pintype "passive"))
      (node (ref "U2") (pin "7") (pinfunction "B02_7") (pintype "bidirectional"))
      (node (ref "U2") (pin "8") (pinfunction "B02_8") (pintype "bidirectional"))
    )
    (net (code "56") (name "MOTOR_B_PWM") (class "Default")
      (node (ref "JP9") (pin "7") (pinfunction "7_7") (pintype "passive"))
      (node (ref "U2") (pin "15") (pinfunction "PWMB_15") (pintype "bidirectional"))
    )
    (net (code "57") (name "MOTOR_STBY") (class "Default")
      (node (ref "JP9") (pin "4") (pinfunction "4_4") (pintype "passive"))
      (node (ref "U2") (pin "19") (pinfunction "STBY_19") (pintype "bidirectional"))
    )
    (net (code "58") (name "Net-(JP1-Pad1)") (class "Default")
      (node (ref "JP1") (pin "1") (pinfunction "1_1") (pintype "passive"))
      (node (ref "R4") (pin "2") (pinfunction "2_2") (pintype "passive"))
    )
    (net (code "59") (name "Net-(JP1-Pad3)") (class "Default")
      (node (ref "JP1") (pin "3") (pinfunction "3_3") (pintype "passive"))
      (node (ref "JP2") (pin "3") (pinfunction "3_3") (pintype "passive"))
      (node (ref "JP3") (pin "3") (pinfunction "3_3") (pintype "passive"))
      (node (ref "JP4") (pin "3") (pinfunction "3_3") (pintype "passive"))
      (node (ref "JP5") (pin "3") (pinfunction "3_3") (pintype "passive"))
      (node (ref "JP6") (pin "3") (pinfunction "3_3") (pintype "passive"))
      (node (ref "JP7") (pin "3") (pinfunction "3_3") (pintype "passive"))
      (node (ref "JP8") (pin "3") (pinfunction "3_3") (pintype "passive"))
      (node (ref "U$13") (pin "D") (pinfunction "D_D") (pintype "passive"))
    )
    (net (code "60") (name "Net-(JP2-Pad1)") (class "Default")
      (node (ref "JP2") (pin "1") (pinfunction "1_1") (pintype "passive"))
      (node (ref "R6") (pin "2") (pinfunction "2_2") (pintype "passive"))
    )
    (net (code "61") (name "Net-(JP3-Pad1)") (class "Default")
      (node (ref "JP3") (pin "1") (pinfunction "1_1") (pintype "passive"))
      (node (ref "R8") (pin "2") (pinfunction "2_2") (pintype "passive"))
    )
    (net (code "62") (name "Net-(JP4-Pad1)") (class "Default")
      (node (ref "JP4") (pin "1") (pinfunction "1_1") (pintype "passive"))
      (node (ref "R10") (pin "2") (pinfunction "2_2") (pintype "passive"))
    )
    (net (code "63") (name "Net-(JP5-Pad1)") (class "Default")
      (node (ref "JP5") (pin "1") (pinfunction "1_1") (pintype "passive"))
      (node (ref "R12") (pin "2") (pinfunction "2_2") (pintype "passive"))
    )
    (net (code "64") (name "Net-(JP6-Pad1)") (class "Default")
      (node (ref "JP6") (pin "1") (pinfunction "1_1") (pintype "passive"))
      (node (ref "R14") (pin "2") (pinfunction "2_2") (pintype "passive"))
    )
    (net (code "65") (name "Net-(JP7-Pad1)") (class "Default")
      (node (ref "JP7") (pin "1") (pinfunction "1_1") (pintype "passive"))
      (node (ref "R16") (pin "2") (pinfunction "2_2") (pintype "passive"))
    )
    (net (code "66") (name "Net-(JP8-Pad1)") (class "Default")
      (node (ref "JP8") (pin "1") (pinfunction "1_1") (pintype "passive"))
      (node (ref "R18") (pin "2") (pinfunction "2_2") (pintype "passive"))
    )
    (net (code "67") (name "Net-(LED1-BA)") (class "Default")
      (node (ref "LED1") (pin "B1") (pinfunction "BA_B1") (pintype "passive"))
      (node (ref "LED2") (pin "B1") (pinfunction "BA_B1") (pintype "passive"))
      (node (ref "LED3") (pin "B1") (pinfunction "BA_B1") (pintype "passive"))
      (node (ref "LED4") (pin "B1") (pinfunction "BA_B1") (pintype "passive"))
      (node (ref "LED5") (pin "B1") (pinfunction "BA_B1") (pintype "passive"))
      (node (ref "LED6") (pin "B1") (pinfunction "BA_B1") (pintype "passive"))
      (node (ref "LED7") (pin "B1") (pinfunction "BA_B1") (pintype "passive"))
      (node (ref "LED8") (pin "B1") (pinfunction "BA_B1") (pintype "passive"))
      (node (ref "R3") (pin "2") (pinfunction "2_2") (pintype "passive"))
    )
    (net (code "68") (name "Net-(LED1-BC)") (class "Default")
      (node (ref "LED1") (pin "B2") (pinfunction "BC_B2") (pintype "passive"))
      (node (ref "LED1") (pin "G2") (pinfunction "GC_G2") (pintype "passive"))
      (node (ref "LED1") (pin "R2") (pinfunction "RC_R2") (pintype "passive"))
      (node (ref "U$4") (pin "D") (pinfunction "D_D") (pintype "passive"))
    )
    (net (code "69") (name "Net-(LED1-GA)") (class "Default")
      (node (ref "LED1") (pin "G1") (pinfunction "GA_G1") (pintype "passive"))
      (node (ref "LED2") (pin "G1") (pinfunction "GA_G1") (pintype "passive"))
      (node (ref "LED3") (pin "G1") (pinfunction "GA_G1") (pintype "passive"))
      (node (ref "LED4") (pin "G1") (pinfunction "GA_G1") (pintype "passive"))
      (node (ref "LED5") (pin "G1") (pinfunction "GA_G1") (pintype "passive"))
      (node (ref "LED6") (pin "G1") (pinfunction "GA_G1") (pintype "passive"))
      (node (ref "LED7") (pin "G1") (pinfunction "GA_G1") (pintype "passive"))
      (node (ref "LED8") (pin "G1") (pinfunction "GA_G1") (pintype "passive"))
      (node (ref "R2") (pin "2") (pinfunction "2_2") (pintype "passive"))
    )
    (net (code "70") (name "Net-(LED1-RA)") (class "Default")
      (node (ref "LED1") (pin "R1") (pinfunction "RA_R1") (pintype "passive"))
      (node (ref "LED2") (pin "R1") (pinfunction "RA_R1") (pintype "passive"))
      (node (ref "LED3") (pin "R1") (pinfunction "RA_R1") (pintype "passive"))
      (node (ref "LED4") (pin "R1") (pinfunction "RA_R1") (pintype "passive"))
      (node (ref "LED5") (pin "R1") (pinfunction "RA_R1") (pintype "passive"))
      (node (ref "LED6") (pin "R1") (pinfunction "RA_R1") (pintype "passive"))
      (node (ref "LED7") (pin "R1") (pinfunction "RA_R1") (pintype "passive"))
      (node (ref "LED8") (pin "R1") (pinfunction "RA_R1") (pintype "passive"))
      (node (ref "R1") (pin "2") (pinfunction "2_2") (pintype "passive"))
    )
    (net (code "71") (name "Net-(LED2-BC)") (class "Default")
      (node (ref "LED2") (pin "B2") (pinfunction "BC_B2") (pintype "passive"))
      (node (ref "LED2") (pin "G2") (pinfunction "GC_G2") (pintype "passive"))
      (node (ref "LED2") (pin "R2") (pinfunction "RC_R2") (pintype "passive"))
      (node (ref "U$5") (pin "D") (pinfunction "D_D") (pintype "passive"))
    )
    (net (code "72") (name "Net-(LED3-BC)") (class "Default")
      (node (ref "LED3") (pin "B2") (pinfunction "BC_B2") (pintype "passive"))
      (node (ref "LED3") (pin "G2") (pinfunction "GC_G2") (pintype "passive"))
      (node (ref "LED3") (pin "R2") (pinfunction "RC_R2") (pintype "passive"))
      (node (ref "U$6") (pin "D") (pinfunction "D_D") (pintype "passive"))
    )
    (net (code "73") (name "Net-(LED4-BC)") (class "Default")
      (node (ref "LED4") (pin "B2") (pinfunction "BC_B2") (pintype "passive"))
      (node (ref "LED4") (pin "G2") (pinfunction "GC_G2") (pintype "passive"))
      (node (ref "LED4") (pin "R2") (pinfunction "RC_R2") (pintype "passive"))
      (node (ref "U$7") (pin "D") (pinfunction "D_D") (pintype "passive"))
    )
    (net (code "74") (name "Net-(LED5-BC)") (class "Default")
      (node (ref "LED5") (pin "B2") (pinfunction "BC_B2") (pintype "passive"))
      (node (ref "LED5") (pin "G2") (pinfunction "GC_G2") (pintype "passive"))
      (node (ref "LED5") (pin "R2") (pinfunction "RC_R2") (pintype "passive"))
      (node (ref "U$8") (pin "D") (pinfunction "D_D") (pintype "passive"))
    )
    (net (code "75") (name "Net-(LED6-BC)") (class "Default")
      (node (ref "LED6") (pin "B2") (pinfunction "BC_B2") (pintype "passive"))
      (node (ref "LED6") (pin "G2") (pinfunction "GC_G2") (pintype "passive"))
      (node (ref "LED6") (pin "R2") (pinfunction "RC_R2") (pintype "passive"))
      (node (ref "U$9") (pin "D") (pinfunction "D_D") (pintype "passive"))
    )
    (net (code "76") (name "Net-(LED7-BC)") (class "Default")
      (node (ref "LED7") (pin "B2") (pinfunction "BC_B2") (pintype "passive"))
      (node (ref "LED7") (pin "G2") (pinfunction "GC_G2") (pintype "passive"))
      (node (ref "LED7") (pin "R2") (pinfunction "RC_R2") (pintype "passive"))
      (node (ref "U$10") (pin "D") (pinfunction "D_D") (pintype "passive"))
    )
    (net (code "77") (name "Net-(LED8-BC)") (class "Default")
      (node (ref "LED8") (pin "B2") (pinfunction "BC_B2") (pintype "passive"))
      (node (ref "LED8") (pin "G2") (pinfunction "GC_G2") (pintype "passive"))
      (node (ref "LED8") (pin "R2") (pinfunction "RC_R2") (pintype "passive"))
      (node (ref "U$11") (pin "D") (pinfunction "D_D") (pintype "passive"))
    )
    (net (code "78") (name "Net-(LED9-PadC)") (class "Default")
      (node (ref "LED9") (pin "C") (pinfunction "C_C") (pintype "passive"))
      (node (ref "R30") (pin "1") (pinfunction "1_1") (pintype "passive"))
    )
    (net (code "79") (name "Net-(LED10-PadC)") (class "Default")
      (node (ref "LED10") (pin "C") (pinfunction "C_C") (pintype "passive"))
      (node (ref "R31") (pin "1") (pinfunction "1_1") (pintype "passive"))
    )
    (net (code "80") (name "Net-(R1-Pad1)") (class "Default")
      (node (ref "R1") (pin "1") (pinfunction "1_1") (pintype "passive"))
      (node (ref "U$1") (pin "S") (pinfunction "S_S") (pintype "passive"))
    )
    (net (code "81") (name "Net-(R2-Pad1)") (class "Default")
      (node (ref "R2") (pin "1") (pinfunction "1_1") (pintype "passive"))
      (node (ref "U$2") (pin "S") (pinfunction "S_S") (pintype "passive"))
    )
    (net (code "82") (name "Net-(R3-Pad1)") (class "Default")
      (node (ref "R3") (pin "1") (pinfunction "1_1") (pintype "passive"))
      (node (ref "U$3") (pin "S") (pinfunction "S_S") (pintype "passive"))
    )
    (net (code "83") (name "Net-(R4-Pad1)") (class "Default")
      (node (ref "R4") (pin "1") (pinfunction "1_1") (pintype "passive"))
      (node (ref "U$12") (pin "S") (pinfunction "S_S") (pintype "passive"))
    )
    (net (code "84") (name "Net-(R6-Pad1)") (class "Default")
      (node (ref "R6") (pin "1") (pinfunction "1_1") (pintype "passive"))
      (node (ref "U$14") (pin "S") (pinfunction "S_S") (pintype "passive"))
    )
    (net (code "85") (name "Net-(R8-Pad1)") (class "Default")
      (node (ref "R8") (pin "1") (pinfunction "1_1") (pintype "passive"))
      (node (ref "U$15") (pin "S") (pinfunction "S_S") (pintype "passive"))
    )
    (net (code "86") (name "Net-(R10-Pad1)") (class "Default")
      (node (ref "R10") (pin "1") (pinfunction "1_1") (pintype "passive"))
      (node (ref "U$16") (pin "S") (pinfunction "S_S") (pintype "passive"))
    )
    (net (code "87") (name "Net-(R12-Pad1)") (class "Default")
      (node (ref "R12") (pin "1") (pinfunction "1_1") (pintype "passive"))
      (node (ref "U$17") (pin "S") (pinfunction "S_S") (pintype "passive"))
    )
    (net (code "88") (name "Net-(R14-Pad1)") (class "Default")
      (node (ref "R14") (pin "1") (pinfunction "1_1") (pintype "passive"))
      (node (ref "U$18") (pin "S") (pinfunction "S_S") (pintype "passive"))
    )
    (net (code "89") (name "Net-(R16-Pad1)") (class "Default")
      (node (ref "R16") (pin "1") (pinfunction "1_1") (pintype "passive"))
      (node (ref "U$19") (pin "S") (pinfunction "S_S") (pintype "passive"))
    )
    (net (code "90") (name "Net-(R18-Pad1)") (class "Default")
      (node (ref "R18") (pin "1") (pinfunction "1_1") (pintype "passive"))
      (node (ref "U$20") (pin "S") (pinfunction "S_S") (pintype "passive"))
    )
    (net (code "91") (name "Net-(R21-Pad1)") (class "Default")
      (node (ref "R21") (pin "1") (pinfunction "1_1") (pintype "passive"))
      (node (ref "U$21") (pin "LED_A") (pinfunction "LED_A_LED_A") (pintype "bidirectional"))
    )
    (net (code "92") (name "Net-(R23-Pad1)") (class "Default")
      (node (ref "R23") (pin "1") (pinfunction "1_1") (pintype "passive"))
      (node (ref "U$22") (pin "LED_A") (pinfunction "LED_A_LED_A") (pintype "bidirectional"))
    )
    (net (code "93") (name "Net-(R25-Pad1)") (class "Default")
      (node (ref "R25") (pin "1") (pinfunction "1_1") (pintype "passive"))
      (node (ref "U$23") (pin "LED_A") (pinfunction "LED_A_LED_A") (pintype "bidirectional"))
    )
    (net (code "94") (name "Net-(R27-Pad1)") (class "Default")
      (node (ref "R27") (pin "1") (pinfunction "1_1") (pintype "passive"))
      (node (ref "U$24") (pin "LED_A") (pinfunction "LED_A_LED_A") (pintype "bidirectional"))
    )
    (net (code "95") (name "PDI_CLK") (class "Default")
      (node (ref "SV1") (pin "5") (pinfunction "5_5") (pintype "passive"))
    )
    (net (code "96") (name "PDI_CLOCK") (class "Default")
      (node (ref "R34") (pin "2") (pinfunction "2_2") (pintype "passive"))
      (node (ref "U1") (pin "57") (pinfunction "~{RESET}/PDI_57") (pintype "bidirectional"))
    )
    (net (code "97") (name "PDI_DATA") (class "Default")
      (node (ref "SV1") (pin "1") (pinfunction "1_1") (pintype "passive"))
      (node (ref "U1") (pin "56") (pinfunction "PDI_56") (pintype "bidirectional"))
    )
    (net (code "98") (name "RPI_RX") (class "Default")
      (node (ref "U$26") (pin "GPIO_15") (pinfunction "GPIO_15_GPIO_15") (pintype "bidirectional"))
    )
    (net (code "99") (name "RPI_TX") (class "Default")
      (node (ref "U$26") (pin "GPIO_14") (pinfunction "GPIO_14_GPIO_14") (pintype "bidirectional"))
    )
    (net (code "100") (name "SCL") (class "Default")
      (node (ref "R32") (pin "2") (pinfunction "2_2") (pintype "passive"))
      (node (ref "U$25") (pin "SCL") (pinfunction "SCL_SCL") (pintype "bidirectional"))
    )
    (net (code "101") (name "SDA") (class "Default")
      (node (ref "R33") (pin "2") (pinfunction "2_2") (pintype "passive"))
      (node (ref "U$25") (pin "SDA") (pinfunction "SDA_SDA") (pintype "bidirectional"))
    )
    (net (code "102") (name "unconnected-(C5-Pad1)") (class "Default")
      (node (ref "C5") (pin "1") (pinfunction "1_1") (pintype "passive"))
    )
    (net (code "103") (name "unconnected-(C5-Pad2)") (class "Default")
      (node (ref "C5") (pin "2") (pinfunction "2_2") (pintype "passive"))
    )
    (net (code "104") (name "unconnected-(SV1-Pad3)") (class "Default")
      (node (ref "SV1") (pin "3") (pinfunction "3_3") (pintype "passive"))
    )
    (net (code "105") (name "unconnected-(SV1-Pad4)") (class "Default")
      (node (ref "SV1") (pin "4") (pinfunction "4_4") (pintype "passive"))
    )
    (net (code "106") (name "unconnected-(U$25-PadA_INT1)") (class "Default")
      (node (ref "U$25") (pin "A_INT1") (pinfunction "A_INT1_A_INT1") (pintype "bidirectional"))
    )
    (net (code "107") (name "unconnected-(U$25-PadG_INT)") (class "Default")
      (node (ref "U$25") (pin "G_INT") (pinfunction "G_INT_G_INT") (pintype "bidirectional"))
    )
    (net (code "108") (name "unconnected-(U$25-PadM_DRDY)") (class "Default")
      (node (ref "U$25") (pin "M_DRDY") (pinfunction "M_DRDY_M_DRDY") (pintype "bidirectional"))
    )
    (net (code "109") (name "unconnected-(U$25-PadP_E0C)") (class "Default")
      (node (ref "U$25") (pin "P_E0C") (pinfunction "P_E0C_P_E0C") (pintype "bidirectional"))
    )
    (net (code "110") (name "unconnected-(U$25-PadP_XCLR)") (class "Default")
      (node (ref "U$25") (pin "P_XCLR") (pinfunction "P_XCLR_P_XCLR") (pintype "bidirectional"))
    )
    (net (code "111") (name "unconnected-(U$26-PadGPIO_0)") (class "Default")
      (node (ref "U$26") (pin "GPIO_0") (pinfunction "GPIO_0_GPIO_0") (pintype "bidirectional"))
    )
    (net (code "112") (name "unconnected-(U$26-PadGPIO_1)") (class "Default")
      (node (ref "U$26") (pin "GPIO_1") (pinfunction "GPIO_1_GPIO_1") (pintype "bidirectional"))
    )
    (net (code "113") (name "unconnected-(U$26-PadGPIO_4)") (class "Default")
      (node (ref "U$26") (pin "GPIO_4") (pinfunction "GPIO_4_GPIO_4") (pintype "bidirectional"))
    )
    (net (code "114") (name "unconnected-(U$26-PadGPIO_7)") (class "Default")
      (node (ref "U$26") (pin "GPIO_7") (pinfunction "GPIO_7_GPIO_7") (pintype "bidirectional"))
    )
    (net (code "115") (name "unconnected-(U$26-PadGPIO_8)") (class "Default")
      (node (ref "U$26") (pin "GPIO_8") (pinfunction "GPIO_8_GPIO_8") (pintype "bidirectional"))
    )
    (net (code "116") (name "unconnected-(U$26-PadGPIO_9)") (class "Default")
      (node (ref "U$26") (pin "GPIO_9") (pinfunction "GPIO_9_GPIO_9") (pintype "bidirectional"))
    )
    (net (code "117") (name "unconnected-(U$26-PadGPIO_10)") (class "Default")
      (node (ref "U$26") (pin "GPIO_10") (pinfunction "GPIO_10_GPIO_10") (pintype "bidirectional"))
    )
    (net (code "118") (name "unconnected-(U$26-PadGPIO_11)") (class "Default")
      (node (ref "U$26") (pin "GPIO_11") (pinfunction "GPIO_11_GPIO_11") (pintype "bidirectional"))
    )
    (net (code "119") (name "unconnected-(U$26-PadGPIO_17)") (class "Default")
      (node (ref "U$26") (pin "GPIO_17") (pinfunction "GPIO_17_GPIO_17") (pintype "bidirectional"))
    )
    (net (code "120") (name "unconnected-(U$26-PadGPIO_18)") (class "Default")
      (node (ref "U$26") (pin "GPIO_18") (pinfunction "GPIO_18_GPIO_18") (pintype "bidirectional"))
    )
    (net (code "121") (name "unconnected-(U$26-PadGPIO_21)") (class "Default")
      (node (ref "U$26") (pin "GPIO_21") (pinfunction "GPIO_21_GPIO_21") (pintype "bidirectional"))
    )
    (net (code "122") (name "unconnected-(U$26-PadGPIO_22)") (class "Default")
      (node (ref "U$26") (pin "GPIO_22") (pinfunction "GPIO_22_GPIO_22") (pintype "bidirectional"))
    )
    (net (code "123") (name "unconnected-(U$26-PadGPIO_23)") (class "Default")
      (node (ref "U$26") (pin "GPIO_23") (pinfunction "GPIO_23_GPIO_23") (pintype "bidirectional"))
    )
    (net (code "124") (name "unconnected-(U$26-PadGPIO_24)") (class "Default")
      (node (ref "U$26") (pin "GPIO_24") (pinfunction "GPIO_24_GPIO_24") (pintype "bidirectional"))
    )
    (net (code "125") (name "unconnected-(U$26-PadGPIO_25)") (class "Default")
      (node (ref "U$26") (pin "GPIO_25") (pinfunction "GPIO_25_GPIO_25") (pintype "bidirectional"))
    )
    (net (code "126") (name "unconnected-(U1-PA0-Pad62)") (class "Default")
      (node (ref "U1") (pin "62") (pinfunction "PA0_62") (pintype "bidirectional"))
    )
    (net (code "127") (name "unconnected-(U1-PA1-Pad63)") (class "Default")
      (node (ref "U1") (pin "63") (pinfunction "PA1_63") (pintype "bidirectional"))
    )
    (net (code "128") (name "unconnected-(U1-PA2-Pad64)") (class "Default")
      (node (ref "U1") (pin "64") (pinfunction "PA2_64") (pintype "bidirectional"))
    )
    (net (code "129") (name "unconnected-(U1-PA3-Pad1)") (class "Default")
      (node (ref "U1") (pin "1") (pinfunction "PA3_1") (pintype "bidirectional"))
    )
    (net (code "130") (name "unconnected-(U1-PA4-Pad2)") (class "Default")
      (node (ref "U1") (pin "2") (pinfunction "PA4_2") (pintype "bidirectional"))
    )
    (net (code "131") (name "unconnected-(U1-PA5-Pad3)") (class "Default")
      (node (ref "U1") (pin "3") (pinfunction "PA5_3") (pintype "bidirectional"))
    )
    (net (code "132") (name "unconnected-(U1-PA6-Pad4)") (class "Default")
      (node (ref "U1") (pin "4") (pinfunction "PA6_4") (pintype "bidirectional"))
    )
    (net (code "133") (name "unconnected-(U1-PA7-Pad5)") (class "Default")
      (node (ref "U1") (pin "5") (pinfunction "PA7_5") (pintype "bidirectional"))
    )
    (net (code "134") (name "unconnected-(U1-PB0-Pad6)") (class "Default")
      (node (ref "U1") (pin "6") (pinfunction "PB0_6") (pintype "bidirectional"))
    )
    (net (code "135") (name "unconnected-(U1-PB1-Pad7)") (class "Default")
      (node (ref "U1") (pin "7") (pinfunction "PB1_7") (pintype "bidirectional"))
    )
    (net (code "136") (name "unconnected-(U1-PB2-Pad8)") (class "Default")
      (node (ref "U1") (pin "8") (pinfunction "PB2_8") (pintype "bidirectional"))
    )
    (net (code "137") (name "unconnected-(U1-PB3-Pad9)") (class "Default")
      (node (ref "U1") (pin "9") (pinfunction "PB3_9") (pintype "bidirectional"))
    )
    (net (code "138") (name "unconnected-(U1-PB4-Pad10)") (class "Default")
      (node (ref "U1") (pin "10") (pinfunction "PB4_10") (pintype "bidirectional"))
    )
    (net (code "139") (name "unconnected-(U1-PB5-Pad11)") (class "Default")
      (node (ref "U1") (pin "11") (pinfunction "PB5_11") (pintype "bidirectional"))
    )
    (net (code "140") (name "unconnected-(U1-PB6-Pad12)") (class "Default")
      (node (ref "U1") (pin "12") (pinfunction "PB6_12") (pintype "bidirectional"))
    )
    (net (code "141") (name "unconnected-(U1-PB7-Pad13)") (class "Default")
      (node (ref "U1") (pin "13") (pinfunction "PB7_13") (pintype "bidirectional"))
    )
    (net (code "142") (name "unconnected-(U1-PC0-Pad16)") (class "Default")
      (node (ref "U1") (pin "16") (pinfunction "PC0_16") (pintype "bidirectional"))
    )
    (net (code "143") (name "unconnected-(U1-PC1-Pad17)") (class "Default")
      (node (ref "U1") (pin "17") (pinfunction "PC1_17") (pintype "bidirectional"))
    )
    (net (code "144") (name "unconnected-(U1-PC2-Pad18)") (class "Default")
      (node (ref "U1") (pin "18") (pinfunction "PC2_18") (pintype "bidirectional"))
    )
    (net (code "145") (name "unconnected-(U1-PC3-Pad19)") (class "Default")
      (node (ref "U1") (pin "19") (pinfunction "PC3_19") (pintype "bidirectional"))
    )
    (net (code "146") (name "unconnected-(U1-PC4-Pad20)") (class "Default")
      (node (ref "U1") (pin "20") (pinfunction "PC4_20") (pintype "bidirectional"))
    )
    (net (code "147") (name "unconnected-(U1-PC5-Pad21)") (class "Default")
      (node (ref "U1") (pin "21") (pinfunction "PC5_21") (pintype "bidirectional"))
    )
    (net (code "148") (name "unconnected-(U1-PC6-Pad22)") (class "Default")
      (node (ref "U1") (pin "22") (pinfunction "PC6_22") (pintype "bidirectional"))
    )
    (net (code "149") (name "unconnected-(U1-PC7-Pad23)") (class "Default")
      (node (ref "U1") (pin "23") (pinfunction "PC7_23") (pintype "bidirectional"))
    )
    (net (code "150") (name "unconnected-(U1-PD0-Pad26)") (class "Default")
      (node (ref "U1") (pin "26") (pinfunction "PD0_26") (pintype "bidirectional"))
    )
    (net (code "151") (name "unconnected-(U1-PD1-Pad27)") (class "Default")
      (node (ref "U1") (pin "27") (pinfunction "PD1_27") (pintype "bidirectional"))
    )
    (net (code "152") (name "unconnected-(U1-PD2-Pad28)") (class "Default")
      (node (ref "U1") (pin "28") (pinfunction "PD2_28") (pintype "bidirectional"))
    )
    (net (code "153") (name "unconnected-(U1-PD3-Pad29)") (class "Default")
      (node (ref "U1") (pin "29") (pinfunction "PD3_29") (pintype "bidirectional"))
    )
    (net (code "154") (name "unconnected-(U1-PD4-Pad30)") (class "Default")
      (node (ref "U1") (pin "30") (pinfunction "PD4_30") (pintype "bidirectional"))
    )
    (net (code "155") (name "unconnected-(U1-PD5-Pad31)") (class "Default")
      (node (ref "U1") (pin "31") (pinfunction "PD5_31") (pintype "bidirectional"))
    )
    (net (code "156") (name "unconnected-(U1-PD6-Pad32)") (class "Default")
      (node (ref "U1") (pin "32") (pinfunction "PD6_32") (pintype "bidirectional"))
    )
    (net (code "157") (name "unconnected-(U1-PD7-Pad33)") (class "Default")
      (node (ref "U1") (pin "33") (pinfunction "PD7_33") (pintype "bidirectional"))
    )
    (net (code "158") (name "unconnected-(U1-PE0-Pad36)") (class "Default")
      (node (ref "U1") (pin "36") (pinfunction "PE0_36") (pintype "bidirectional"))
    )
    (net (code "159") (name "unconnected-(U1-PE1-Pad37)") (class "Default")
      (node (ref "U1") (pin "37") (pinfunction "PE1_37") (pintype "bidirectional"))
    )
    (net (code "160") (name "unconnected-(U1-PE2-Pad38)") (class "Default")
      (node (ref "U1") (pin "38") (pinfunction "PE2_38") (pintype "bidirectional"))
    )
    (net (code "161") (name "unconnected-(U1-PE3-Pad39)") (class "Default")
      (node (ref "U1") (pin "39") (pinfunction "PE3_39") (pintype "bidirectional"))
    )
    (net (code "162") (name "unconnected-(U1-PE4-Pad40)") (class "Default")
      (node (ref "U1") (pin "40") (pinfunction "PE4_40") (pintype "bidirectional"))
    )
    (net (code "163") (name "unconnected-(U1-PE5-Pad41)") (class "Default")
      (node (ref "U1") (pin "41") (pinfunction "PE5_41") (pintype "bidirectional"))
    )
    (net (code "164") (name "unconnected-(U1-PE6-Pad42)") (class "Default")
      (node (ref "U1") (pin "42") (pinfunction "PE6_42") (pintype "bidirectional"))
    )
    (net (code "165") (name "unconnected-(U1-PE7-Pad43)") (class "Default")
      (node (ref "U1") (pin "43") (pinfunction "PE7_43") (pintype "bidirectional"))
    )
    (net (code "166") (name "unconnected-(U1-PF0-Pad46)") (class "Default")
      (node (ref "U1") (pin "46") (pinfunction "PF0_46") (pintype "bidirectional"))
    )
    (net (code "167") (name "unconnected-(U1-PF1-Pad47)") (class "Default")
      (node (ref "U1") (pin "47") (pinfunction "PF1_47") (pintype "bidirectional"))
    )
    (net (code "168") (name "unconnected-(U1-PF2-Pad48)") (class "Default")
      (node (ref "U1") (pin "48") (pinfunction "PF2_48") (pintype "bidirectional"))
    )
    (net (code "169") (name "unconnected-(U1-PF3-Pad49)") (class "Default")
      (node (ref "U1") (pin "49") (pinfunction "PF3_49") (pintype "bidirectional"))
    )
    (net (code "170") (name "unconnected-(U1-PF4-Pad50)") (class "Default")
      (node (ref "U1") (pin "50") (pinfunction "PF4_50") (pintype "bidirectional"))
    )
    (net (code "171") (name "unconnected-(U1-PF5-Pad51)") (class "Default")
      (node (ref "U1") (pin "51") (pinfunction "PF5_51") (pintype "bidirectional"))
    )
    (net (code "172") (name "unconnected-(U1-PF6-Pad54)") (class "Default")
      (node (ref "U1") (pin "54") (pinfunction "PF6_54") (pintype "bidirectional"))
    )
    (net (code "173") (name "unconnected-(U1-PF7-Pad55)") (class "Default")
      (node (ref "U1") (pin "55") (pinfunction "PF7_55") (pintype "bidirectional"))
    )
    (net (code "174") (name "unconnected-(U1-PR0-Pad58)") (class "Default")
      (node (ref "U1") (pin "58") (pinfunction "PR0_58") (pintype "bidirectional"))
    )
    (net (code "175") (name "unconnected-(U1-PR1-Pad59)") (class "Default")
      (node (ref "U1") (pin "59") (pinfunction "PR1_59") (pintype "bidirectional"))
    )
  )
)
